# AdcUnit.net
KiCad netlist of a schematic drawn in Altium Designer
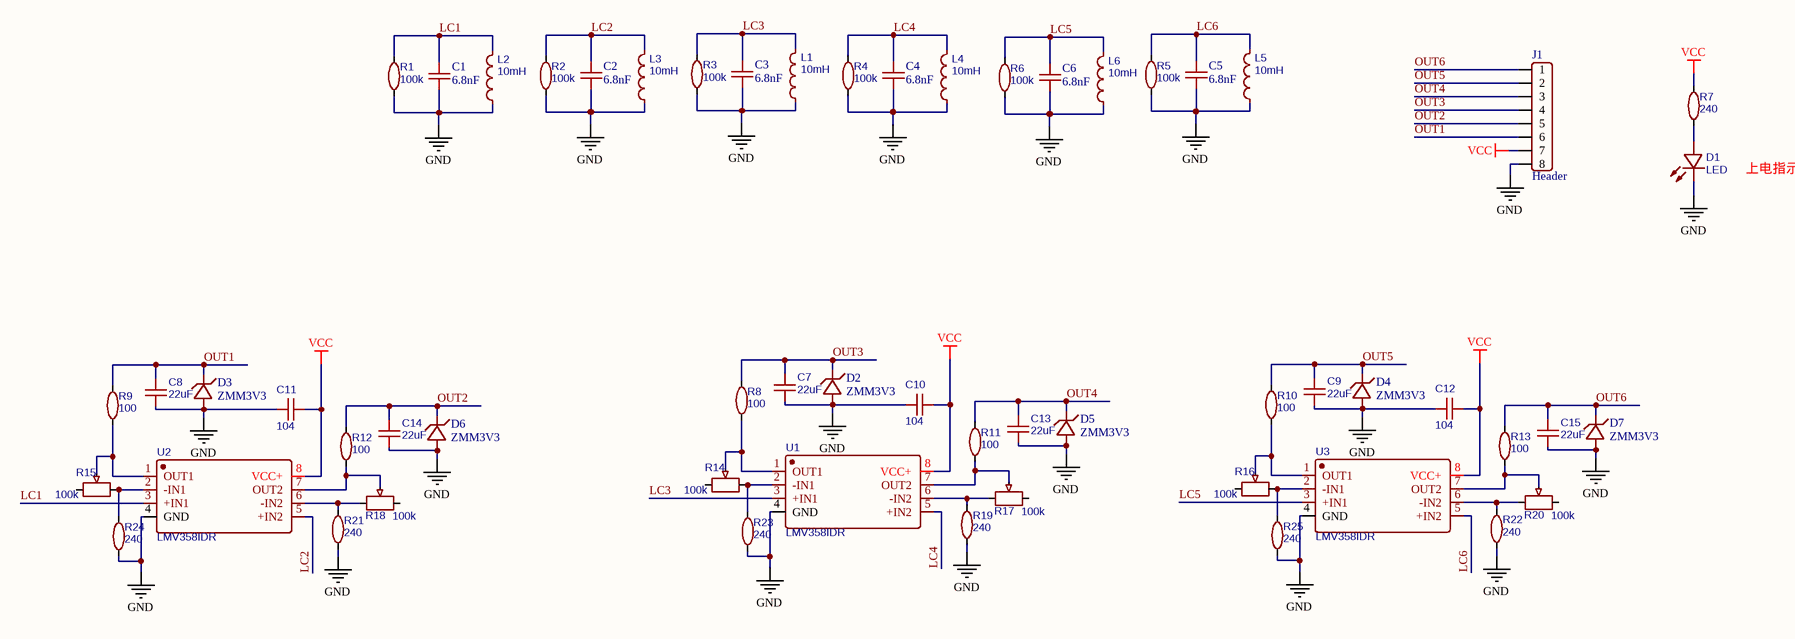
[diagram p0: AdcUnit.SchDoc]

(export (version "E")
  (design (tool "Eeschema 10.0.6"))
  (components
    (comp (ref "C1") (value "6.8nF") (footprint "CAP3") (libsource (lib "LTC_Library1") (part "CAP_聚苯电容")))
    (comp (ref "C2") (value "6.8nF") (footprint "CAP3") (libsource (lib "LTC_Library1") (part "CAP_聚苯电容")))
    (comp (ref "C3") (value "6.8nF") (footprint "CAP3") (libsource (lib "LTC_Library1") (part "CAP_聚苯电容")))
    (comp (ref "C4") (value "6.8nF") (footprint "CAP3") (libsource (lib "LTC_Library1") (part "CAP_聚苯电容")))
    (comp (ref "C5") (value "6.8nF") (footprint "CAP3") (libsource (lib "LTC_Library1") (part "CAP_聚苯电容")))
    (comp (ref "C6") (value "6.8nF") (footprint "CAP3") (libsource (lib "LTC_Library1") (part "CAP_聚苯电容")))
    (comp (ref "C7")
      (value "22uF")
      (footprint "CAP_0603")
      (fields
        (field (name "BOM_SUPPLIER PART") "C307348")
        (field (name "BOM_MANUFACTURER PART") "CL10B104KB8WPNC")
        (field (name "CONTRIBUTOR") "LCSC")
      )
      (libsource (lib "LTC_Library1") (part "CAP_0603"))
    )
    (comp (ref "C8")
      (value "22uF")
      (footprint "CAP_0603")
      (fields
        (field (name "BOM_SUPPLIER PART") "C307348")
        (field (name "BOM_MANUFACTURER PART") "CL10B104KB8WPNC")
        (field (name "CONTRIBUTOR") "LCSC")
      )
      (libsource (lib "LTC_Library1") (part "CAP_0603"))
    )
    (comp (ref "C9")
      (value "22uF")
      (footprint "CAP_0603")
      (fields
        (field (name "BOM_SUPPLIER PART") "C307348")
        (field (name "BOM_MANUFACTURER PART") "CL10B104KB8WPNC")
        (field (name "CONTRIBUTOR") "LCSC")
      )
      (libsource (lib "LTC_Library1") (part "CAP_0603"))
    )
    (comp (ref "C10")
      (value "104")
      (footprint "CAP_0603")
      (fields
        (field (name "BOM_SUPPLIER PART") "C307348")
        (field (name "BOM_MANUFACTURER PART") "CL10B104KB8WPNC")
        (field (name "CONTRIBUTOR") "LCSC")
      )
      (libsource (lib "LTC_Library1") (part "CAP_0603"))
    )
    (comp (ref "C11")
      (value "104")
      (footprint "CAP_0603")
      (fields
        (field (name "BOM_SUPPLIER PART") "C307348")
        (field (name "BOM_MANUFACTURER PART") "CL10B104KB8WPNC")
        (field (name "CONTRIBUTOR") "LCSC")
      )
      (libsource (lib "LTC_Library1") (part "CAP_0603"))
    )
    (comp (ref "C12")
      (value "104")
      (footprint "CAP_0603")
      (fields
        (field (name "BOM_SUPPLIER PART") "C307348")
        (field (name "BOM_MANUFACTURER PART") "CL10B104KB8WPNC")
        (field (name "CONTRIBUTOR") "LCSC")
      )
      (libsource (lib "LTC_Library1") (part "CAP_0603"))
    )
    (comp (ref "C13")
      (value "22uF")
      (footprint "CAP_0603")
      (fields
        (field (name "BOM_SUPPLIER PART") "C307348")
        (field (name "BOM_MANUFACTURER PART") "CL10B104KB8WPNC")
        (field (name "CONTRIBUTOR") "LCSC")
      )
      (libsource (lib "LTC_Library1") (part "CAP_0603"))
    )
    (comp (ref "C14")
      (value "22uF")
      (footprint "CAP_0603")
      (fields
        (field (name "BOM_SUPPLIER PART") "C307348")
        (field (name "BOM_MANUFACTURER PART") "CL10B104KB8WPNC")
        (field (name "CONTRIBUTOR") "LCSC")
      )
      (libsource (lib "LTC_Library1") (part "CAP_0603"))
    )
    (comp (ref "C15")
      (value "22uF")
      (footprint "CAP_0603")
      (fields
        (field (name "BOM_SUPPLIER PART") "C307348")
        (field (name "BOM_MANUFACTURER PART") "CL10B104KB8WPNC")
        (field (name "CONTRIBUTOR") "LCSC")
      )
      (libsource (lib "LTC_Library1") (part "CAP_0603"))
    )
    (comp (ref "D1")
      (value "LED")
      (footprint "LED_0603_B")
      (description "发光LED")
      (fields
        (field (name "BOM_MANUFACTURER PART") "D-G080508G1")
        (field (name "BOM_SUPPLIER PART") "C107402")
        (field (name "CONTRIBUTOR") "LCSC")
      )
      (libsource (lib "LTC_Library1") (part "LED_0603"))
    )
    (comp (ref "D2") (value "ZMM3V3") (footprint "LL34") (libsource (lib "LTC_Library1") (part "ZMM3V3")))
    (comp (ref "D3") (value "ZMM3V3") (footprint "LL34") (libsource (lib "LTC_Library1") (part "ZMM3V3")))
    (comp (ref "D4") (value "ZMM3V3") (footprint "LL34") (libsource (lib "LTC_Library1") (part "ZMM3V3")))
    (comp (ref "D5") (value "ZMM3V3") (footprint "LL34") (libsource (lib "LTC_Library1") (part "ZMM3V3")))
    (comp (ref "D6") (value "ZMM3V3") (footprint "LL34") (libsource (lib "LTC_Library1") (part "ZMM3V3")))
    (comp (ref "D7") (value "ZMM3V3") (footprint "LL34") (libsource (lib "LTC_Library1") (part "ZMM3V3")))
    (comp (ref "J1")
      (value "Header")
      (footprint "Header 2.54X8")
      (libsource (lib "LTC_Library1") (part "Header 2.54_8"))
    )
    (comp (ref "L1")
      (value "10mH")
      (footprint "Inductor_8x10")
      (fields
        (field (name "BOM_SUPPLIER PART") "C295130")
        (field (name "BOM_MANUFACTURER PART") "NLV25T-330J-EF")
        (field (name "CONTRIBUTOR") "LCSC")
      )
      (libsource (lib "LTC_Library1") (part "Inductor"))
    )
    (comp (ref "L2")
      (value "10mH")
      (footprint "Inductor_8x10")
      (fields
        (field (name "BOM_SUPPLIER PART") "C295130")
        (field (name "BOM_MANUFACTURER PART") "NLV25T-330J-EF")
        (field (name "CONTRIBUTOR") "LCSC")
      )
      (libsource (lib "LTC_Library1") (part "Inductor"))
    )
    (comp (ref "L3")
      (value "10mH")
      (footprint "Inductor_8x10")
      (fields
        (field (name "BOM_SUPPLIER PART") "C295130")
        (field (name "BOM_MANUFACTURER PART") "NLV25T-330J-EF")
        (field (name "CONTRIBUTOR") "LCSC")
      )
      (libsource (lib "LTC_Library1") (part "Inductor"))
    )
    (comp (ref "L4")
      (value "10mH")
      (footprint "Inductor_8x10")
      (fields
        (field (name "BOM_SUPPLIER PART") "C295130")
        (field (name "BOM_MANUFACTURER PART") "NLV25T-330J-EF")
        (field (name "CONTRIBUTOR") "LCSC")
      )
      (libsource (lib "LTC_Library1") (part "Inductor"))
    )
    (comp (ref "L5")
      (value "10mH")
      (footprint "Inductor_8x10")
      (fields
        (field (name "BOM_SUPPLIER PART") "C295130")
        (field (name "BOM_MANUFACTURER PART") "NLV25T-330J-EF")
        (field (name "CONTRIBUTOR") "LCSC")
      )
      (libsource (lib "LTC_Library1") (part "Inductor"))
    )
    (comp (ref "L6")
      (value "10mH")
      (footprint "Inductor_8x10")
      (fields
        (field (name "BOM_SUPPLIER PART") "C295130")
        (field (name "BOM_MANUFACTURER PART") "NLV25T-330J-EF")
        (field (name "CONTRIBUTOR") "LCSC")
      )
      (libsource (lib "LTC_Library1") (part "Inductor"))
    )
    (comp (ref "R1")
      (value "100k")
      (footprint "RES_0603")
      (fields
        (field (name "BOM_MANUFACTURER PART") "RC0402JR-07100KL")
        (field (name "BOM_SUPPLIER PART") "C106234")
      )
      (libsource (lib "LTC_Library1") (part "RES_0603"))
    )
    (comp (ref "R2")
      (value "100k")
      (footprint "RES_0603")
      (fields
        (field (name "BOM_MANUFACTURER PART") "RC0402JR-07100KL")
        (field (name "BOM_SUPPLIER PART") "C106234")
      )
      (libsource (lib "LTC_Library1") (part "RES_0603"))
    )
    (comp (ref "R3")
      (value "100k")
      (footprint "RES_0603")
      (fields
        (field (name "BOM_MANUFACTURER PART") "RC0402JR-07100KL")
        (field (name "BOM_SUPPLIER PART") "C106234")
      )
      (libsource (lib "LTC_Library1") (part "RES_0603"))
    )
    (comp (ref "R4")
      (value "100k")
      (footprint "RES_0603")
      (fields
        (field (name "BOM_MANUFACTURER PART") "RC0402JR-07100KL")
        (field (name "BOM_SUPPLIER PART") "C106234")
      )
      (libsource (lib "LTC_Library1") (part "RES_0603"))
    )
    (comp (ref "R5")
      (value "100k")
      (footprint "RES_0603")
      (fields
        (field (name "BOM_MANUFACTURER PART") "RC0402JR-07100KL")
        (field (name "BOM_SUPPLIER PART") "C106234")
      )
      (libsource (lib "LTC_Library1") (part "RES_0603"))
    )
    (comp (ref "R6")
      (value "100k")
      (footprint "RES_0603")
      (fields
        (field (name "BOM_MANUFACTURER PART") "RC0402JR-07100KL")
        (field (name "BOM_SUPPLIER PART") "C106234")
      )
      (libsource (lib "LTC_Library1") (part "RES_0603"))
    )
    (comp (ref "R7")
      (value "240")
      (footprint "RES_0603")
      (fields
        (field (name "BOM_MANUFACTURER PART") "RC0402JR-07100KL")
        (field (name "BOM_SUPPLIER PART") "C106234")
      )
      (libsource (lib "LTC_Library1") (part "RES_0603"))
    )
    (comp (ref "R8")
      (value "100")
      (footprint "RES_0603")
      (fields
        (field (name "BOM_MANUFACTURER PART") "RC0402JR-07100KL")
        (field (name "BOM_SUPPLIER PART") "C106234")
      )
      (libsource (lib "LTC_Library1") (part "RES_0603"))
    )
    (comp (ref "R9")
      (value "100")
      (footprint "RES_0603")
      (fields
        (field (name "BOM_MANUFACTURER PART") "RC0402JR-07100KL")
        (field (name "BOM_SUPPLIER PART") "C106234")
      )
      (libsource (lib "LTC_Library1") (part "RES_0603"))
    )
    (comp (ref "R10")
      (value "100")
      (footprint "RES_0603")
      (fields
        (field (name "BOM_MANUFACTURER PART") "RC0402JR-07100KL")
        (field (name "BOM_SUPPLIER PART") "C106234")
      )
      (libsource (lib "LTC_Library1") (part "RES_0603"))
    )
    (comp (ref "R11")
      (value "100")
      (footprint "RES_0603")
      (fields
        (field (name "BOM_MANUFACTURER PART") "RC0402JR-07100KL")
        (field (name "BOM_SUPPLIER PART") "C106234")
      )
      (libsource (lib "LTC_Library1") (part "RES_0603"))
    )
    (comp (ref "R12")
      (value "100")
      (footprint "RES_0603")
      (fields
        (field (name "BOM_MANUFACTURER PART") "RC0402JR-07100KL")
        (field (name "BOM_SUPPLIER PART") "C106234")
      )
      (libsource (lib "LTC_Library1") (part "RES_0603"))
    )
    (comp (ref "R13")
      (value "100")
      (footprint "RES_0603")
      (fields
        (field (name "BOM_MANUFACTURER PART") "RC0402JR-07100KL")
        (field (name "BOM_SUPPLIER PART") "C106234")
      )
      (libsource (lib "LTC_Library1") (part "RES_0603"))
    )
    (comp (ref "R14")
      (value "100k")
      (footprint "RES_POT-3296W")
      (description "可调电阻3296W")
      (fields
        (field (name "BOM_SUPPLIER PART") "C118963")
        (field (name "BOM_MANUFACTURER PART") "3296W-1-104")
        (field (name "CONTRIBUTOR") "LCSC")
      )
      (libsource (lib "LTC_Library1") (part "RES_POT-3296W"))
    )
    (comp (ref "R15")
      (value "100k")
      (footprint "RES_POT-3296W")
      (description "可调电阻3296W")
      (fields
        (field (name "BOM_SUPPLIER PART") "C118963")
        (field (name "BOM_MANUFACTURER PART") "3296W-1-104")
        (field (name "CONTRIBUTOR") "LCSC")
      )
      (libsource (lib "LTC_Library1") (part "RES_POT-3296W"))
    )
    (comp (ref "R16")
      (value "100k")
      (footprint "RES_POT-3296W")
      (description "可调电阻3296W")
      (fields
        (field (name "BOM_SUPPLIER PART") "C118963")
        (field (name "BOM_MANUFACTURER PART") "3296W-1-104")
        (field (name "CONTRIBUTOR") "LCSC")
      )
      (libsource (lib "LTC_Library1") (part "RES_POT-3296W"))
    )
    (comp (ref "R17")
      (value "100k")
      (footprint "RES_POT-3296W")
      (description "可调电阻3296W")
      (fields
        (field (name "BOM_SUPPLIER PART") "C118963")
        (field (name "BOM_MANUFACTURER PART") "3296W-1-104")
        (field (name "CONTRIBUTOR") "LCSC")
      )
      (libsource (lib "LTC_Library1") (part "RES_POT-3296W"))
    )
    (comp (ref "R18")
      (value "100k")
      (footprint "RES_POT-3296W")
      (description "可调电阻3296W")
      (fields
        (field (name "BOM_SUPPLIER PART") "C118963")
        (field (name "BOM_MANUFACTURER PART") "3296W-1-104")
        (field (name "CONTRIBUTOR") "LCSC")
      )
      (libsource (lib "LTC_Library1") (part "RES_POT-3296W"))
    )
    (comp (ref "R19")
      (value "240")
      (footprint "RES_0603")
      (fields
        (field (name "BOM_MANUFACTURER PART") "RC0402JR-07100KL")
        (field (name "BOM_SUPPLIER PART") "C106234")
      )
      (libsource (lib "LTC_Library1") (part "RES_0603"))
    )
    (comp (ref "R20")
      (value "100k")
      (footprint "RES_POT-3296W")
      (description "可调电阻3296W")
      (fields
        (field (name "BOM_SUPPLIER PART") "C118963")
        (field (name "BOM_MANUFACTURER PART") "3296W-1-104")
        (field (name "CONTRIBUTOR") "LCSC")
      )
      (libsource (lib "LTC_Library1") (part "RES_POT-3296W"))
    )
    (comp (ref "R21")
      (value "240")
      (footprint "RES_0603")
      (fields
        (field (name "BOM_MANUFACTURER PART") "RC0402JR-07100KL")
        (field (name "BOM_SUPPLIER PART") "C106234")
      )
      (libsource (lib "LTC_Library1") (part "RES_0603"))
    )
    (comp (ref "R22")
      (value "240")
      (footprint "RES_0603")
      (fields
        (field (name "BOM_MANUFACTURER PART") "RC0402JR-07100KL")
        (field (name "BOM_SUPPLIER PART") "C106234")
      )
      (libsource (lib "LTC_Library1") (part "RES_0603"))
    )
    (comp (ref "R23")
      (value "240")
      (footprint "RES_0603")
      (fields
        (field (name "BOM_MANUFACTURER PART") "RC0402JR-07100KL")
        (field (name "BOM_SUPPLIER PART") "C106234")
      )
      (libsource (lib "LTC_Library1") (part "RES_0603"))
    )
    (comp (ref "R24")
      (value "240")
      (footprint "RES_0603")
      (fields
        (field (name "BOM_MANUFACTURER PART") "RC0402JR-07100KL")
        (field (name "BOM_SUPPLIER PART") "C106234")
      )
      (libsource (lib "LTC_Library1") (part "RES_0603"))
    )
    (comp (ref "R25")
      (value "240")
      (footprint "RES_0603")
      (fields
        (field (name "BOM_MANUFACTURER PART") "RC0402JR-07100KL")
        (field (name "BOM_SUPPLIER PART") "C106234")
      )
      (libsource (lib "LTC_Library1") (part "RES_0603"))
    )
    (comp (ref "U1")
      (value "LMV358IDR")
      (footprint "SOIC-8_150MIL")
      (fields (field (name "BOM_SUPPLIER PART") "C63813"))
      (libsource (lib "LTC_Library1") (part "LMV358IDR"))
    )
    (comp (ref "U2")
      (value "LMV358IDR")
      (footprint "SOIC-8_150MIL")
      (fields (field (name "BOM_SUPPLIER PART") "C63813"))
      (libsource (lib "LTC_Library1") (part "LMV358IDR"))
    )
    (comp (ref "U3")
      (value "LMV358IDR")
      (footprint "SOIC-8_150MIL")
      (fields (field (name "BOM_SUPPLIER PART") "C63813"))
      (libsource (lib "LTC_Library1") (part "LMV358IDR"))
    )
  )
  (nets
    (net (code "1") (name "/LC1") (class "Default")
      (node (ref "C1") (pin "1") (pinfunction "1_1") (pintype "passive"))
      (node (ref "L2") (pin "2") (pinfunction "2_2") (pintype "passive"))
      (node (ref "R1") (pin "2") (pinfunction "2_2") (pintype "passive"))
      (node (ref "U2") (pin "3") (pinfunction "+IN1_3") (pintype "passive"))
    )
    (net (code "2") (name "/LC2") (class "Default")
      (node (ref "C2") (pin "1") (pinfunction "1_1") (pintype "passive"))
      (node (ref "L3") (pin "2") (pinfunction "2_2") (pintype "passive"))
      (node (ref "R2") (pin "2") (pinfunction "2_2") (pintype "passive"))
      (node (ref "U2") (pin "5") (pinfunction "+IN2_5") (pintype "passive"))
    )
    (net (code "3") (name "/LC3") (class "Default")
      (node (ref "C3") (pin "1") (pinfunction "1_1") (pintype "passive"))
      (node (ref "L1") (pin "2") (pinfunction "2_2") (pintype "passive"))
      (node (ref "R3") (pin "2") (pinfunction "2_2") (pintype "passive"))
      (node (ref "U1") (pin "3") (pinfunction "+IN1_3") (pintype "passive"))
    )
    (net (code "4") (name "/LC4") (class "Default")
      (node (ref "C4") (pin "1") (pinfunction "1_1") (pintype "passive"))
      (node (ref "L4") (pin "2") (pinfunction "2_2") (pintype "passive"))
      (node (ref "R4") (pin "2") (pinfunction "2_2") (pintype "passive"))
      (node (ref "U1") (pin "5") (pinfunction "+IN2_5") (pintype "passive"))
    )
    (net (code "5") (name "/LC5") (class "Default")
      (node (ref "C6") (pin "1") (pinfunction "1_1") (pintype "passive"))
      (node (ref "L6") (pin "2") (pinfunction "2_2") (pintype "passive"))
      (node (ref "R6") (pin "2") (pinfunction "2_2") (pintype "passive"))
      (node (ref "U3") (pin "3") (pinfunction "+IN1_3") (pintype "passive"))
    )
    (net (code "6") (name "/LC6") (class "Default")
      (node (ref "C5") (pin "1") (pinfunction "1_1") (pintype "passive"))
      (node (ref "L5") (pin "2") (pinfunction "2_2") (pintype "passive"))
      (node (ref "R5") (pin "2") (pinfunction "2_2") (pintype "passive"))
      (node (ref "U3") (pin "5") (pinfunction "+IN2_5") (pintype "passive"))
    )
    (net (code "7") (name "/OUT1") (class "Default")
      (node (ref "C8") (pin "1") (pinfunction "1_1") (pintype "passive"))
      (node (ref "D3") (pin "2") (pinfunction "C_2") (pintype "passive"))
      (node (ref "J1") (pin "6") (pinfunction "6_6") (pintype "passive"))
      (node (ref "R9") (pin "2") (pinfunction "2_2") (pintype "passive"))
    )
    (net (code "8") (name "/OUT2") (class "Default")
      (node (ref "C14") (pin "1") (pinfunction "1_1") (pintype "passive"))
      (node (ref "D6") (pin "2") (pinfunction "C_2") (pintype "passive"))
      (node (ref "J1") (pin "5") (pinfunction "5_5") (pintype "passive"))
      (node (ref "R12") (pin "2") (pinfunction "2_2") (pintype "passive"))
    )
    (net (code "9") (name "/OUT3") (class "Default")
      (node (ref "C7") (pin "1") (pinfunction "1_1") (pintype "passive"))
      (node (ref "D2") (pin "2") (pinfunction "C_2") (pintype "passive"))
      (node (ref "J1") (pin "4") (pinfunction "4_4") (pintype "passive"))
      (node (ref "R8") (pin "2") (pinfunction "2_2") (pintype "passive"))
    )
    (net (code "10") (name "/OUT4") (class "Default")
      (node (ref "C13") (pin "1") (pinfunction "1_1") (pintype "passive"))
      (node (ref "D5") (pin "2") (pinfunction "C_2") (pintype "passive"))
      (node (ref "J1") (pin "3") (pinfunction "3_3") (pintype "passive"))
      (node (ref "R11") (pin "2") (pinfunction "2_2") (pintype "passive"))
    )
    (net (code "11") (name "/OUT5") (class "Default")
      (node (ref "C9") (pin "1") (pinfunction "1_1") (pintype "passive"))
      (node (ref "D4") (pin "2") (pinfunction "C_2") (pintype "passive"))
      (node (ref "J1") (pin "2") (pinfunction "2_2") (pintype "passive"))
      (node (ref "R10") (pin "2") (pinfunction "2_2") (pintype "passive"))
    )
    (net (code "12") (name "/OUT6") (class "Default")
      (node (ref "C15") (pin "1") (pinfunction "1_1") (pintype "passive"))
      (node (ref "D7") (pin "2") (pinfunction "C_2") (pintype "passive"))
      (node (ref "J1") (pin "1") (pinfunction "1_1") (pintype "passive"))
      (node (ref "R13") (pin "2") (pinfunction "2_2") (pintype "passive"))
    )
    (net (code "13") (name "GND") (class "Default")
      (node (ref "C1") (pin "2") (pinfunction "2_2") (pintype "passive"))
      (node (ref "C10") (pin "1") (pinfunction "1_1") (pintype "passive"))
      (node (ref "C11") (pin "1") (pinfunction "1_1") (pintype "passive"))
      (node (ref "C12") (pin "1") (pinfunction "1_1") (pintype "passive"))
      (node (ref "C13") (pin "2") (pinfunction "2_2") (pintype "passive"))
      (node (ref "C14") (pin "2") (pinfunction "2_2") (pintype "passive"))
      (node (ref "C15") (pin "2") (pinfunction "2_2") (pintype "passive"))
      (node (ref "C2") (pin "2") (pinfunction "2_2") (pintype "passive"))
      (node (ref "C3") (pin "2") (pinfunction "2_2") (pintype "passive"))
      (node (ref "C4") (pin "2") (pinfunction "2_2") (pintype "passive"))
      (node (ref "C5") (pin "2") (pinfunction "2_2") (pintype "passive"))
      (node (ref "C6") (pin "2") (pinfunction "2_2") (pintype "passive"))
      (node (ref "C7") (pin "2") (pinfunction "2_2") (pintype "passive"))
      (node (ref "C8") (pin "2") (pinfunction "2_2") (pintype "passive"))
      (node (ref "C9") (pin "2") (pinfunction "2_2") (pintype "passive"))
      (node (ref "D1") (pin "C") (pinfunction "C_C") (pintype "passive"))
      (node (ref "D2") (pin "1") (pinfunction "A_1") (pintype "passive"))
      (node (ref "D3") (pin "1") (pinfunction "A_1") (pintype "passive"))
      (node (ref "D4") (pin "1") (pinfunction "A_1") (pintype "passive"))
      (node (ref "D5") (pin "1") (pinfunction "A_1") (pintype "passive"))
      (node (ref "D6") (pin "1") (pinfunction "A_1") (pintype "passive"))
      (node (ref "D7") (pin "1") (pinfunction "A_1") (pintype "passive"))
      (node (ref "J1") (pin "8") (pinfunction "8_8") (pintype "passive"))
      (node (ref "L1") (pin "1") (pinfunction "1_1") (pintype "passive"))
      (node (ref "L2") (pin "1") (pinfunction "1_1") (pintype "passive"))
      (node (ref "L3") (pin "1") (pinfunction "1_1") (pintype "passive"))
      (node (ref "L4") (pin "1") (pinfunction "1_1") (pintype "passive"))
      (node (ref "L5") (pin "1") (pinfunction "1_1") (pintype "passive"))
      (node (ref "L6") (pin "1") (pinfunction "1_1") (pintype "passive"))
      (node (ref "R1") (pin "1") (pinfunction "1_1") (pintype "passive"))
      (node (ref "R19") (pin "1") (pinfunction "1_1") (pintype "passive"))
      (node (ref "R2") (pin "1") (pinfunction "1_1") (pintype "passive"))
      (node (ref "R21") (pin "1") (pinfunction "1_1") (pintype "passive"))
      (node (ref "R22") (pin "1") (pinfunction "1_1") (pintype "passive"))
      (node (ref "R23") (pin "1") (pinfunction "1_1") (pintype "passive"))
      (node (ref "R24") (pin "1") (pinfunction "1_1") (pintype "passive"))
      (node (ref "R25") (pin "1") (pinfunction "1_1") (pintype "passive"))
      (node (ref "R3") (pin "1") (pinfunction "1_1") (pintype "passive"))
      (node (ref "R4") (pin "1") (pinfunction "1_1") (pintype "passive"))
      (node (ref "R5") (pin "1") (pinfunction "1_1") (pintype "passive"))
      (node (ref "R6") (pin "1") (pinfunction "1_1") (pintype "passive"))
      (node (ref "U1") (pin "4") (pinfunction "GND_4") (pintype "passive"))
      (node (ref "U2") (pin "4") (pinfunction "GND_4") (pintype "passive"))
      (node (ref "U3") (pin "4") (pinfunction "GND_4") (pintype "passive"))
    )
    (net (code "14") (name "Net-(D1-PadA)") (class "Default")
      (node (ref "D1") (pin "A") (pinfunction "A_A") (pintype "passive"))
      (node (ref "R7") (pin "1") (pinfunction "1_1") (pintype "passive"))
    )
    (net (code "15") (name "Net-(U1--IN1)") (class "Default")
      (node (ref "R14") (pin "3") (pinfunction "3_3") (pintype "passive"))
      (node (ref "R23") (pin "2") (pinfunction "2_2") (pintype "passive"))
      (node (ref "U1") (pin "2") (pinfunction "-IN1_2") (pintype "passive"))
    )
    (net (code "16") (name "Net-(U1--IN2)") (class "Default")
      (node (ref "R17") (pin "1") (pinfunction "1_1") (pintype "passive"))
      (node (ref "R19") (pin "2") (pinfunction "2_2") (pintype "passive"))
      (node (ref "U1") (pin "6") (pinfunction "-IN2_6") (pintype "passive"))
    )
    (net (code "17") (name "Net-(U1-OUT1)") (class "Default")
      (node (ref "R14") (pin "2") (pinfunction "2_2") (pintype "passive"))
      (node (ref "R8") (pin "1") (pinfunction "1_1") (pintype "passive"))
      (node (ref "U1") (pin "1") (pinfunction "OUT1_1") (pintype "passive"))
    )
    (net (code "18") (name "Net-(U1-OUT2)") (class "Default")
      (node (ref "R11") (pin "1") (pinfunction "1_1") (pintype "passive"))
      (node (ref "R17") (pin "2") (pinfunction "2_2") (pintype "passive"))
      (node (ref "U1") (pin "7") (pinfunction "OUT2_7") (pintype "passive"))
    )
    (net (code "19") (name "Net-(U2--IN1)") (class "Default")
      (node (ref "R15") (pin "3") (pinfunction "3_3") (pintype "passive"))
      (node (ref "R24") (pin "2") (pinfunction "2_2") (pintype "passive"))
      (node (ref "U2") (pin "2") (pinfunction "-IN1_2") (pintype "passive"))
    )
    (net (code "20") (name "Net-(U2--IN2)") (class "Default")
      (node (ref "R18") (pin "1") (pinfunction "1_1") (pintype "passive"))
      (node (ref "R21") (pin "2") (pinfunction "2_2") (pintype "passive"))
      (node (ref "U2") (pin "6") (pinfunction "-IN2_6") (pintype "passive"))
    )
    (net (code "21") (name "Net-(U2-OUT1)") (class "Default")
      (node (ref "R15") (pin "2") (pinfunction "2_2") (pintype "passive"))
      (node (ref "R9") (pin "1") (pinfunction "1_1") (pintype "passive"))
      (node (ref "U2") (pin "1") (pinfunction "OUT1_1") (pintype "passive"))
    )
    (net (code "22") (name "Net-(U2-OUT2)") (class "Default")
      (node (ref "R12") (pin "1") (pinfunction "1_1") (pintype "passive"))
      (node (ref "R18") (pin "2") (pinfunction "2_2") (pintype "passive"))
      (node (ref "U2") (pin "7") (pinfunction "OUT2_7") (pintype "passive"))
    )
    (net (code "23") (name "Net-(U3--IN1)") (class "Default")
      (node (ref "R16") (pin "3") (pinfunction "3_3") (pintype "passive"))
      (node (ref "R25") (pin "2") (pinfunction "2_2") (pintype "passive"))
      (node (ref "U3") (pin "2") (pinfunction "-IN1_2") (pintype "passive"))
    )
    (net (code "24") (name "Net-(U3--IN2)") (class "Default")
      (node (ref "R20") (pin "1") (pinfunction "1_1") (pintype "passive"))
      (node (ref "R22") (pin "2") (pinfunction "2_2") (pintype "passive"))
      (node (ref "U3") (pin "6") (pinfunction "-IN2_6") (pintype "passive"))
    )
    (net (code "25") (name "Net-(U3-OUT1)") (class "Default")
      (node (ref "R10") (pin "1") (pinfunction "1_1") (pintype "passive"))
      (node (ref "R16") (pin "2") (pinfunction "2_2") (pintype "passive"))
      (node (ref "U3") (pin "1") (pinfunction "OUT1_1") (pintype "passive"))
    )
    (net (code "26") (name "Net-(U3-OUT2)") (class "Default")
      (node (ref "R13") (pin "1") (pinfunction "1_1") (pintype "passive"))
      (node (ref "R20") (pin "2") (pinfunction "2_2") (pintype "passive"))
      (node (ref "U3") (pin "7") (pinfunction "OUT2_7") (pintype "passive"))
    )
    (net (code "27") (name "VCC") (class "Default")
      (node (ref "C10") (pin "2") (pinfunction "2_2") (pintype "passive"))
      (node (ref "C11") (pin "2") (pinfunction "2_2") (pintype "passive"))
      (node (ref "C12") (pin "2") (pinfunction "2_2") (pintype "passive"))
      (node (ref "J1") (pin "7") (pinfunction "7_7") (pintype "passive"))
      (node (ref "R7") (pin "2") (pinfunction "2_2") (pintype "passive"))
      (node (ref "U1") (pin "8") (pinfunction "VCC+_8") (pintype "passive"))
      (node (ref "U2") (pin "8") (pinfunction "VCC+_8") (pintype "passive"))
      (node (ref "U3") (pin "8") (pinfunction "VCC+_8") (pintype "passive"))
    )
    (net (code "28") (name "unconnected-(R14-Pad1)") (class "Default")
      (node (ref "R14") (pin "1") (pinfunction "1_1") (pintype "passive"))
    )
    (net (code "29") (name "unconnected-(R15-Pad1)") (class "Default")
      (node (ref "R15") (pin "1") (pinfunction "1_1") (pintype "passive"))
    )
    (net (code "30") (name "unconnected-(R16-Pad1)") (class "Default")
      (node (ref "R16") (pin "1") (pinfunction "1_1") (pintype "passive"))
    )
    (net (code "31") (name "unconnected-(R17-Pad3)") (class "Default")
      (node (ref "R17") (pin "3") (pinfunction "3_3") (pintype "passive"))
    )
    (net (code "32") (name "unconnected-(R18-Pad3)") (class "Default")
      (node (ref "R18") (pin "3") (pinfunction "3_3") (pintype "passive"))
    )
    (net (code "33") (name "unconnected-(R20-Pad3)") (class "Default")
      (node (ref "R20") (pin "3") (pinfunction "3_3") (pintype "passive"))
    )
  )
)
